# ethernet_jack_cnc_shield.net
KiCad netlist of a schematic drawn in EAGLE
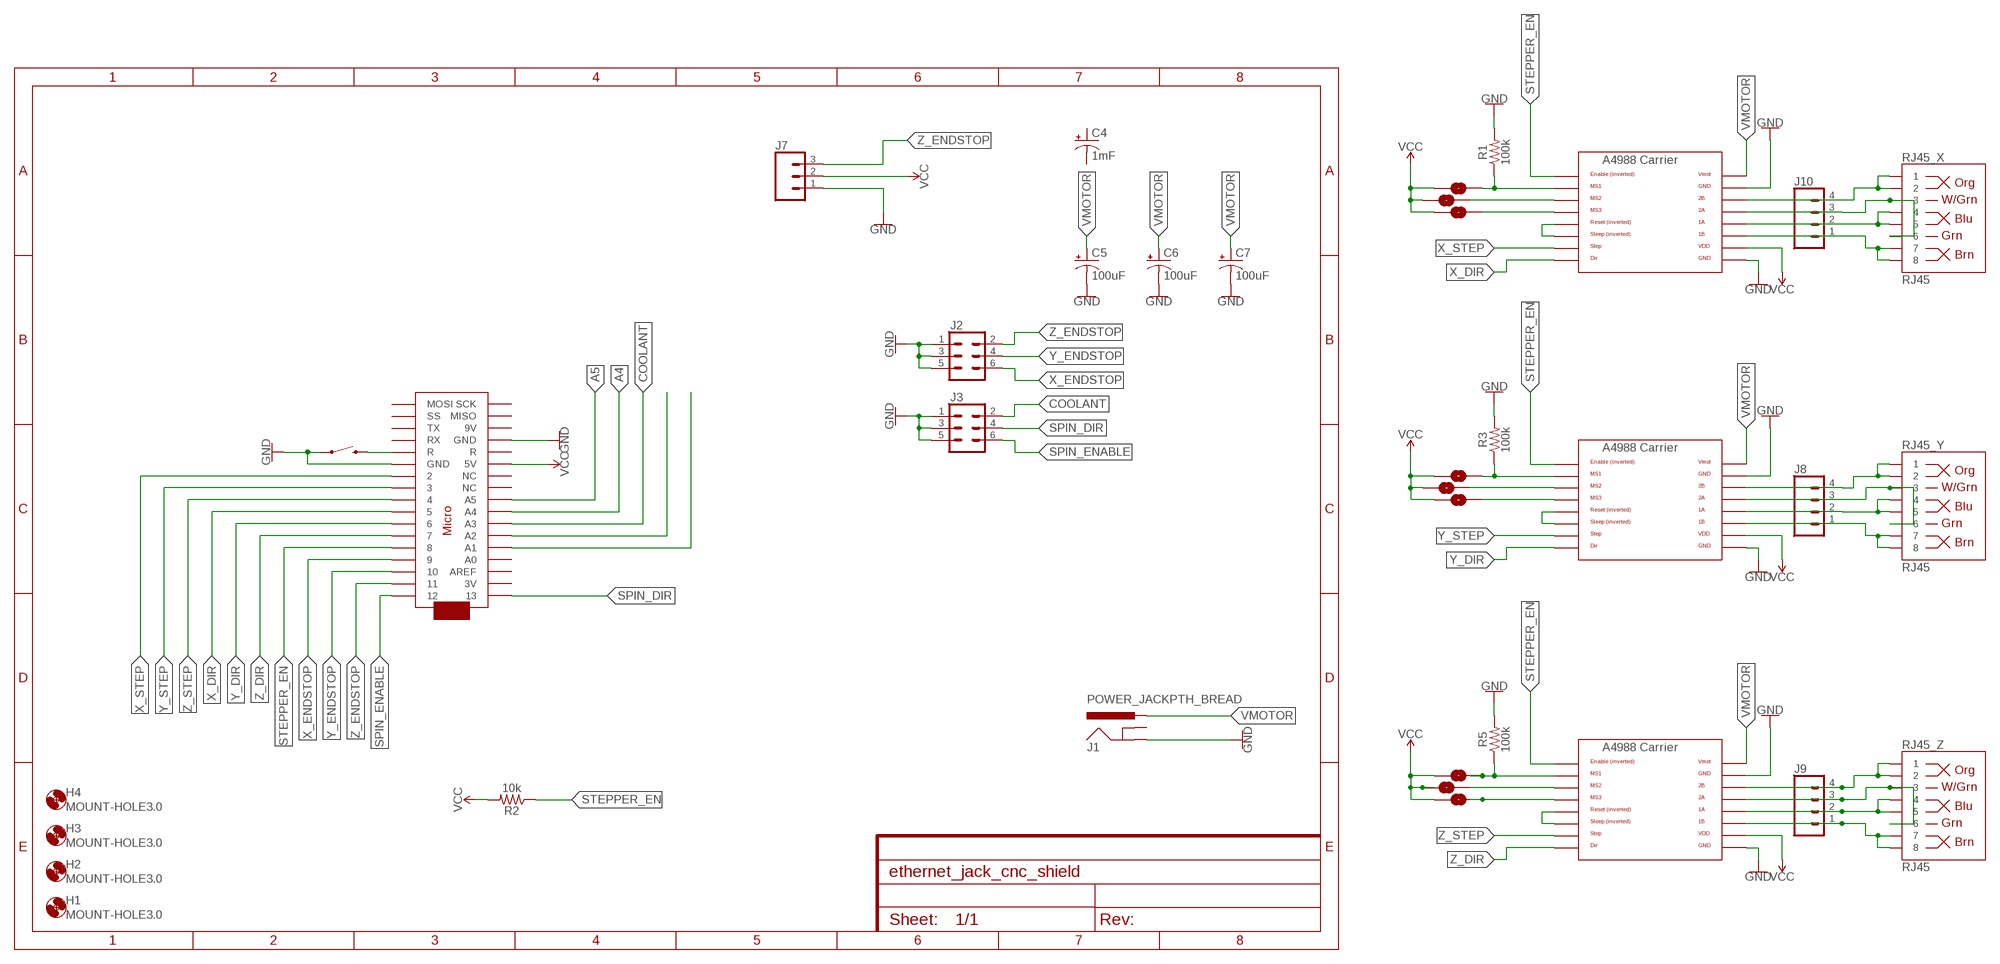
[diagram p0: schematic, sheet 1]

(export (version "E")
  (design (tool "Eeschema 10.0.6"))
  (components
    (comp (ref "C4")
      (value "1mF")
      (footprint "eagle-import:CPOL-RADIAL-5MM-10MM")
      (libsource (lib "eagle-import") (part "1000UF-RADIAL-5MM-25V-20%"))
    )
    (comp (ref "C5")
      (value "100uF")
      (footprint "eagle-import:CPOL-RADIAL-2.5MM-6.5MM")
      (libsource (lib "eagle-import") (part "100UF-POLAR-RADIAL-2.5MM-25V-20%"))
    )
    (comp (ref "C6")
      (value "100uF")
      (footprint "eagle-import:CPOL-RADIAL-2.5MM-6.5MM")
      (libsource (lib "eagle-import") (part "100UF-POLAR-RADIAL-2.5MM-25V-20%"))
    )
    (comp (ref "C7")
      (value "100uF")
      (footprint "eagle-import:CPOL-RADIAL-2.5MM-6.5MM")
      (libsource (lib "eagle-import") (part "100UF-POLAR-RADIAL-2.5MM-25V-20%"))
    )
    (comp (ref "H1")
      (value "MOUNT-HOLE3.0")
      (footprint "eagle-import:3,0")
      (libsource (lib "eagle-import") (part "MOUNT-HOLE3.0"))
    )
    (comp (ref "H2")
      (value "MOUNT-HOLE3.0")
      (footprint "eagle-import:3,0")
      (libsource (lib "eagle-import") (part "MOUNT-HOLE3.0"))
    )
    (comp (ref "H3")
      (value "MOUNT-HOLE3.0")
      (footprint "eagle-import:3,0")
      (libsource (lib "eagle-import") (part "MOUNT-HOLE3.0"))
    )
    (comp (ref "H4")
      (value "MOUNT-HOLE3.0")
      (footprint "eagle-import:3,0")
      (libsource (lib "eagle-import") (part "MOUNT-HOLE3.0"))
    )
    (comp (ref "J1")
      (value "POWER_JACKPTH_BREAD")
      (footprint "eagle-import:POWER_JACK_PTH_BREAD")
      (libsource (lib "eagle-import") (part "POWER_JACKPTH_BREAD"))
    )
    (comp (ref "J2")
      (value "CONN_03X2NO_SILK")
      (footprint "eagle-import:2X3-NS")
      (libsource (lib "eagle-import") (part "CONN_03X2NO_SILK"))
    )
    (comp (ref "J3")
      (value "CONN_03X2NO_SILK")
      (footprint "eagle-import:2X3-NS")
      (libsource (lib "eagle-import") (part "CONN_03X2NO_SILK"))
    )
    (comp (ref "J7")
      (value "CONN_03")
      (footprint "eagle-import:1X03")
      (libsource (lib "eagle-import") (part "CONN_03"))
    )
    (comp (ref "J8")
      (value "CONN_04")
      (footprint "eagle-import:1X04")
      (libsource (lib "eagle-import") (part "CONN_04"))
    )
    (comp (ref "J9")
      (value "CONN_04")
      (footprint "eagle-import:1X04")
      (libsource (lib "eagle-import") (part "CONN_04"))
    )
    (comp (ref "J10")
      (value "CONN_04")
      (footprint "eagle-import:1X04")
      (libsource (lib "eagle-import") (part "CONN_04"))
    )
    (comp (ref "JP1")
      (value "JUMPER-SMT_2_NO_SILK_ROUND")
      (footprint "eagle-import:SMT-JUMPER_2_NO_SILK_ROUND")
      (libsource (lib "eagle-import") (part "JUMPER-SMT_2_NO_SILK_ROUND"))
    )
    (comp (ref "JP2")
      (value "JUMPER-SMT_2_NO_SILK_ROUND")
      (footprint "eagle-import:SMT-JUMPER_2_NO_SILK_ROUND")
      (libsource (lib "eagle-import") (part "JUMPER-SMT_2_NO_SILK_ROUND"))
    )
    (comp (ref "JP3")
      (value "JUMPER-SMT_2_NO_SILK_ROUND")
      (footprint "eagle-import:SMT-JUMPER_2_NO_SILK_ROUND")
      (libsource (lib "eagle-import") (part "JUMPER-SMT_2_NO_SILK_ROUND"))
    )
    (comp (ref "JP4")
      (value "JUMPER-SMT_2_NO_SILK_ROUND")
      (footprint "eagle-import:SMT-JUMPER_2_NO_SILK_ROUND")
      (libsource (lib "eagle-import") (part "JUMPER-SMT_2_NO_SILK_ROUND"))
    )
    (comp (ref "JP5")
      (value "JUMPER-SMT_2_NO_SILK_ROUND")
      (footprint "eagle-import:SMT-JUMPER_2_NO_SILK_ROUND")
      (libsource (lib "eagle-import") (part "JUMPER-SMT_2_NO_SILK_ROUND"))
    )
    (comp (ref "JP6")
      (value "JUMPER-SMT_2_NO_SILK_ROUND")
      (footprint "eagle-import:SMT-JUMPER_2_NO_SILK_ROUND")
      (libsource (lib "eagle-import") (part "JUMPER-SMT_2_NO_SILK_ROUND"))
    )
    (comp (ref "JP7")
      (value "JUMPER-SMT_2_NO_SILK_ROUND")
      (footprint "eagle-import:SMT-JUMPER_2_NO_SILK_ROUND")
      (libsource (lib "eagle-import") (part "JUMPER-SMT_2_NO_SILK_ROUND"))
    )
    (comp (ref "JP8")
      (value "JUMPER-SMT_2_NO_SILK_ROUND")
      (footprint "eagle-import:SMT-JUMPER_2_NO_SILK_ROUND")
      (libsource (lib "eagle-import") (part "JUMPER-SMT_2_NO_SILK_ROUND"))
    )
    (comp (ref "JP9")
      (value "JUMPER-SMT_2_NO_SILK_ROUND")
      (footprint "eagle-import:SMT-JUMPER_2_NO_SILK_ROUND")
      (libsource (lib "eagle-import") (part "JUMPER-SMT_2_NO_SILK_ROUND"))
    )
    (comp (ref "R1")
      (value "100k")
      (footprint "eagle-import:1206")
      (libsource (lib "eagle-import") (part "RESISTOR1206"))
    )
    (comp (ref "R2")
      (value "10k")
      (footprint "eagle-import:1206")
      (libsource (lib "eagle-import") (part "RESISTOR1206"))
    )
    (comp (ref "R3")
      (value "100k")
      (footprint "eagle-import:1206")
      (libsource (lib "eagle-import") (part "RESISTOR1206"))
    )
    (comp (ref "R5")
      (value "100k")
      (footprint "eagle-import:1206")
      (libsource (lib "eagle-import") (part "RESISTOR1206"))
    )
    (comp (ref "RJ45_X")
      (value "RJ45")
      (footprint "eagle-import:RJ45-8")
      (libsource (lib "eagle-import") (part "RJ45-8"))
    )
    (comp (ref "RJ45_Y")
      (value "RJ45")
      (footprint "eagle-import:RJ45-8")
      (libsource (lib "eagle-import") (part "RJ45-8"))
    )
    (comp (ref "RJ45_Z")
      (value "RJ45")
      (footprint "eagle-import:RJ45-8")
      (libsource (lib "eagle-import") (part "RJ45-8"))
    )
    (comp (ref "S1")
      (value "MOMENTARY-SWITCH-SPST-PTH-RIGHT-ANGLE-KIT")
      (footprint "eagle-import:TACTILE_SWITCH_PTH_RIGHT_ANGLE_KIT")
      (libsource (lib "eagle-import") (part "MOMENTARY-SWITCH-SPST-PTH-RIGHT-ANGLE-KIT"))
    )
    (comp (ref "U$1")
      (value "ARDUINOMICRO")
      (footprint "eagle-import:ARDUINOMICRO")
      (libsource (lib "eagle-import") (part "ARDUINOMICRO"))
    )
    (comp (ref "U$2")
      (value "A4988BREAKOUT")
      (footprint "eagle-import:A4988BREAKOUT")
      (libsource (lib "eagle-import") (part "A4988BREAKOUT"))
    )
    (comp (ref "U$3")
      (value "A4988BREAKOUT")
      (footprint "eagle-import:A4988BREAKOUT")
      (libsource (lib "eagle-import") (part "A4988BREAKOUT"))
    )
    (comp (ref "U$4")
      (value "A4988BREAKOUT")
      (footprint "eagle-import:A4988BREAKOUT")
      (libsource (lib "eagle-import") (part "A4988BREAKOUT"))
    )
  )
  (nets
    (net (code "1") (name "A4") (class "Default")
      (node (ref "U$1") (pin "P$27") (pinfunction "A4_P$27") (pintype "bidirectional"))
    )
    (net (code "2") (name "A5") (class "Default")
      (node (ref "U$1") (pin "P$26") (pinfunction "A5_P$26") (pintype "bidirectional"))
    )
    (net (code "3") (name "COOLANT") (class "Default")
      (node (ref "J3") (pin "2") (pinfunction "2_2") (pintype "bidirectional"))
      (node (ref "U$1") (pin "P$28") (pinfunction "A3_P$28") (pintype "bidirectional"))
    )
    (net (code "4") (name "GND") (class "Default")
      (node (ref "C5") (pin "2") (pinfunction "-_2") (pintype "passive"))
      (node (ref "C6") (pin "2") (pinfunction "-_2") (pintype "passive"))
      (node (ref "C7") (pin "2") (pinfunction "-_2") (pintype "passive"))
      (node (ref "J1") (pin "GND") (pinfunction "GND_GND") (pintype "bidirectional"))
      (node (ref "J2") (pin "1") (pinfunction "1_1") (pintype "bidirectional"))
      (node (ref "J2") (pin "3") (pinfunction "3_3") (pintype "bidirectional"))
      (node (ref "J2") (pin "5") (pinfunction "5_5") (pintype "bidirectional"))
      (node (ref "J3") (pin "1") (pinfunction "1_1") (pintype "bidirectional"))
      (node (ref "J3") (pin "3") (pinfunction "3_3") (pintype "bidirectional"))
      (node (ref "J3") (pin "5") (pinfunction "5_5") (pintype "bidirectional"))
      (node (ref "J7") (pin "1") (pinfunction "1_1") (pintype "passive"))
      (node (ref "R1") (pin "2") (pinfunction "2_2") (pintype "passive"))
      (node (ref "R3") (pin "2") (pinfunction "2_2") (pintype "passive"))
      (node (ref "R5") (pin "2") (pinfunction "2_2") (pintype "passive"))
      (node (ref "S1") (pin "1") (pinfunction "1_1") (pintype "passive"))
      (node (ref "U$1") (pin "P$12") (pinfunction "GND_P$12") (pintype "bidirectional"))
      (node (ref "U$1") (pin "P$21") (pinfunction "GND_P$21") (pintype "bidirectional"))
      (node (ref "U$2") (pin "GND") (pinfunction "GND_GND") (pintype "power_in"))
      (node (ref "U$2") (pin "GND@0") (pinfunction "GND_GND@0") (pintype "power_in"))
      (node (ref "U$3") (pin "GND") (pinfunction "GND_GND") (pintype "power_in"))
      (node (ref "U$3") (pin "GND@0") (pinfunction "GND_GND@0") (pintype "power_in"))
      (node (ref "U$4") (pin "GND") (pinfunction "GND_GND") (pintype "power_in"))
      (node (ref "U$4") (pin "GND@0") (pinfunction "GND_GND@0") (pintype "power_in"))
    )
    (net (code "5") (name "Net-(J8-Pad1)") (class "Default")
      (node (ref "J8") (pin "1") (pinfunction "1_1") (pintype "passive"))
      (node (ref "RJ45_Y") (pin "7") (pinfunction "7_7") (pintype "bidirectional"))
      (node (ref "RJ45_Y") (pin "8") (pinfunction "8_8") (pintype "bidirectional"))
      (node (ref "U$2") (pin "1B") (pinfunction "1B_1B") (pintype "output"))
    )
    (net (code "6") (name "Net-(J8-Pad2)") (class "Default")
      (node (ref "J8") (pin "2") (pinfunction "2_2") (pintype "passive"))
      (node (ref "RJ45_Y") (pin "4") (pinfunction "4_4") (pintype "bidirectional"))
      (node (ref "RJ45_Y") (pin "5") (pinfunction "5_5") (pintype "bidirectional"))
      (node (ref "U$2") (pin "1A") (pinfunction "1A_1A") (pintype "output"))
    )
    (net (code "7") (name "Net-(J8-Pad3)") (class "Default")
      (node (ref "J8") (pin "3") (pinfunction "3_3") (pintype "passive"))
      (node (ref "RJ45_Y") (pin "3") (pinfunction "3_3") (pintype "bidirectional"))
      (node (ref "RJ45_Y") (pin "6") (pinfunction "6_6") (pintype "bidirectional"))
      (node (ref "U$2") (pin "2A") (pinfunction "2A_2A") (pintype "output"))
    )
    (net (code "8") (name "Net-(J8-Pad4)") (class "Default")
      (node (ref "J8") (pin "4") (pinfunction "4_4") (pintype "passive"))
      (node (ref "RJ45_Y") (pin "1") (pinfunction "1_1") (pintype "bidirectional"))
      (node (ref "RJ45_Y") (pin "2") (pinfunction "2_2") (pintype "bidirectional"))
      (node (ref "U$2") (pin "2B") (pinfunction "2B_2B") (pintype "output"))
    )
    (net (code "9") (name "Net-(J9-Pad1)") (class "Default")
      (node (ref "J9") (pin "1") (pinfunction "1_1") (pintype "passive"))
      (node (ref "RJ45_Z") (pin "7") (pinfunction "7_7") (pintype "bidirectional"))
      (node (ref "RJ45_Z") (pin "8") (pinfunction "8_8") (pintype "bidirectional"))
      (node (ref "U$3") (pin "1B") (pinfunction "1B_1B") (pintype "output"))
    )
    (net (code "10") (name "Net-(J9-Pad2)") (class "Default")
      (node (ref "J9") (pin "2") (pinfunction "2_2") (pintype "passive"))
      (node (ref "RJ45_Z") (pin "4") (pinfunction "4_4") (pintype "bidirectional"))
      (node (ref "RJ45_Z") (pin "5") (pinfunction "5_5") (pintype "bidirectional"))
      (node (ref "U$3") (pin "1A") (pinfunction "1A_1A") (pintype "output"))
    )
    (net (code "11") (name "Net-(J9-Pad3)") (class "Default")
      (node (ref "J9") (pin "3") (pinfunction "3_3") (pintype "passive"))
      (node (ref "RJ45_Z") (pin "3") (pinfunction "3_3") (pintype "bidirectional"))
      (node (ref "RJ45_Z") (pin "6") (pinfunction "6_6") (pintype "bidirectional"))
      (node (ref "U$3") (pin "2A") (pinfunction "2A_2A") (pintype "output"))
    )
    (net (code "12") (name "Net-(J9-Pad4)") (class "Default")
      (node (ref "J9") (pin "4") (pinfunction "4_4") (pintype "passive"))
      (node (ref "RJ45_Z") (pin "1") (pinfunction "1_1") (pintype "bidirectional"))
      (node (ref "RJ45_Z") (pin "2") (pinfunction "2_2") (pintype "bidirectional"))
      (node (ref "U$3") (pin "2B") (pinfunction "2B_2B") (pintype "output"))
    )
    (net (code "13") (name "Net-(J10-Pad1)") (class "Default")
      (node (ref "J10") (pin "1") (pinfunction "1_1") (pintype "passive"))
      (node (ref "RJ45_X") (pin "7") (pinfunction "7_7") (pintype "bidirectional"))
      (node (ref "RJ45_X") (pin "8") (pinfunction "8_8") (pintype "bidirectional"))
      (node (ref "U$4") (pin "1B") (pinfunction "1B_1B") (pintype "output"))
    )
    (net (code "14") (name "Net-(J10-Pad2)") (class "Default")
      (node (ref "J10") (pin "2") (pinfunction "2_2") (pintype "passive"))
      (node (ref "RJ45_X") (pin "4") (pinfunction "4_4") (pintype "bidirectional"))
      (node (ref "RJ45_X") (pin "5") (pinfunction "5_5") (pintype "bidirectional"))
      (node (ref "U$4") (pin "1A") (pinfunction "1A_1A") (pintype "output"))
    )
    (net (code "15") (name "Net-(J10-Pad3)") (class "Default")
      (node (ref "J10") (pin "3") (pinfunction "3_3") (pintype "passive"))
      (node (ref "RJ45_X") (pin "3") (pinfunction "3_3") (pintype "bidirectional"))
      (node (ref "RJ45_X") (pin "6") (pinfunction "6_6") (pintype "bidirectional"))
      (node (ref "U$4") (pin "2A") (pinfunction "2A_2A") (pintype "output"))
    )
    (net (code "16") (name "Net-(J10-Pad4)") (class "Default")
      (node (ref "J10") (pin "4") (pinfunction "4_4") (pintype "passive"))
      (node (ref "RJ45_X") (pin "1") (pinfunction "1_1") (pintype "bidirectional"))
      (node (ref "RJ45_X") (pin "2") (pinfunction "2_2") (pintype "bidirectional"))
      (node (ref "U$4") (pin "2B") (pinfunction "2B_2B") (pintype "output"))
    )
    (net (code "17") (name "Net-(JP1-Pad2)") (class "Default")
      (node (ref "JP1") (pin "2") (pinfunction "2_2") (pintype "passive"))
      (node (ref "R3") (pin "1") (pinfunction "1_1") (pintype "passive"))
      (node (ref "U$2") (pin "MS1") (pinfunction "MS1_MS1") (pintype "input"))
    )
    (net (code "18") (name "Net-(JP2-Pad2)") (class "Default")
      (node (ref "JP2") (pin "2") (pinfunction "2_2") (pintype "passive"))
      (node (ref "U$2") (pin "MS2") (pinfunction "MS2_MS2") (pintype "input"))
    )
    (net (code "19") (name "Net-(JP3-Pad2)") (class "Default")
      (node (ref "JP3") (pin "2") (pinfunction "2_2") (pintype "passive"))
      (node (ref "R5") (pin "1") (pinfunction "1_1") (pintype "passive"))
      (node (ref "U$3") (pin "MS1") (pinfunction "MS1_MS1") (pintype "input"))
    )
    (net (code "20") (name "Net-(JP4-Pad2)") (class "Default")
      (node (ref "JP4") (pin "2") (pinfunction "2_2") (pintype "passive"))
      (node (ref "R1") (pin "1") (pinfunction "1_1") (pintype "passive"))
      (node (ref "U$4") (pin "MS1") (pinfunction "MS1_MS1") (pintype "input"))
    )
    (net (code "21") (name "Net-(JP5-Pad2)") (class "Default")
      (node (ref "JP5") (pin "2") (pinfunction "2_2") (pintype "passive"))
      (node (ref "U$4") (pin "MS2") (pinfunction "MS2_MS2") (pintype "input"))
    )
    (net (code "22") (name "Net-(JP6-Pad2)") (class "Default")
      (node (ref "JP6") (pin "2") (pinfunction "2_2") (pintype "passive"))
      (node (ref "U$4") (pin "MS3") (pinfunction "MS3_MS3") (pintype "input"))
    )
    (net (code "23") (name "Net-(JP7-Pad2)") (class "Default")
      (node (ref "JP7") (pin "2") (pinfunction "2_2") (pintype "passive"))
      (node (ref "U$2") (pin "MS3") (pinfunction "MS3_MS3") (pintype "input"))
    )
    (net (code "24") (name "Net-(JP8-Pad2)") (class "Default")
      (node (ref "JP8") (pin "2") (pinfunction "2_2") (pintype "passive"))
      (node (ref "U$3") (pin "MS2") (pinfunction "MS2_MS2") (pintype "input"))
    )
    (net (code "25") (name "Net-(JP9-Pad2)") (class "Default")
      (node (ref "JP9") (pin "2") (pinfunction "2_2") (pintype "passive"))
      (node (ref "U$3") (pin "MS3") (pinfunction "MS3_MS3") (pintype "input"))
    )
    (net (code "26") (name "Net-(S1-Pad2)") (class "Default")
      (node (ref "S1") (pin "2") (pinfunction "2_2") (pintype "passive"))
      (node (ref "U$1") (pin "P$22") (pinfunction "R_P$22") (pintype "bidirectional"))
    )
    (net (code "27") (name "Net-(U$2-SLEEP)") (class "Default")
      (node (ref "U$2") (pin "RST") (pinfunction "RST_RST") (pintype "input"))
      (node (ref "U$2") (pin "SLP") (pinfunction "SLEEP_SLP") (pintype "input"))
    )
    (net (code "28") (name "Net-(U$3-SLEEP)") (class "Default")
      (node (ref "U$3") (pin "RST") (pinfunction "RST_RST") (pintype "input"))
      (node (ref "U$3") (pin "SLP") (pinfunction "SLEEP_SLP") (pintype "input"))
    )
    (net (code "29") (name "Net-(U$4-SLEEP)") (class "Default")
      (node (ref "U$4") (pin "RST") (pinfunction "RST_RST") (pintype "input"))
      (node (ref "U$4") (pin "SLP") (pinfunction "SLEEP_SLP") (pintype "input"))
    )
    (net (code "30") (name "SPIN_DIR") (class "Default")
      (node (ref "J3") (pin "4") (pinfunction "4_4") (pintype "bidirectional"))
      (node (ref "U$1") (pin "P$34") (pinfunction "13_P$34") (pintype "bidirectional"))
    )
    (net (code "31") (name "SPIN_ENABLE") (class "Default")
      (node (ref "J3") (pin "6") (pinfunction "6_6") (pintype "bidirectional"))
      (node (ref "U$1") (pin "P$1") (pinfunction "12_P$1") (pintype "bidirectional"))
    )
    (net (code "32") (name "STEPPER_EN") (class "Default")
      (node (ref "R2") (pin "1") (pinfunction "1_1") (pintype "passive"))
      (node (ref "U$1") (pin "P$5") (pinfunction "8_P$5") (pintype "bidirectional"))
      (node (ref "U$2") (pin "EN") (pinfunction "EN_EN") (pintype "input"))
      (node (ref "U$3") (pin "EN") (pinfunction "EN_EN") (pintype "input"))
      (node (ref "U$4") (pin "EN") (pinfunction "EN_EN") (pintype "input"))
    )
    (net (code "33") (name "VCC") (class "Default")
      (node (ref "J7") (pin "2") (pinfunction "2_2") (pintype "passive"))
      (node (ref "JP1") (pin "1") (pinfunction "1_1") (pintype "passive"))
      (node (ref "JP2") (pin "1") (pinfunction "1_1") (pintype "passive"))
      (node (ref "JP3") (pin "1") (pinfunction "1_1") (pintype "passive"))
      (node (ref "JP4") (pin "1") (pinfunction "1_1") (pintype "passive"))
      (node (ref "JP5") (pin "1") (pinfunction "1_1") (pintype "passive"))
      (node (ref "JP6") (pin "1") (pinfunction "1_1") (pintype "passive"))
      (node (ref "JP7") (pin "1") (pinfunction "1_1") (pintype "passive"))
      (node (ref "JP8") (pin "1") (pinfunction "1_1") (pintype "passive"))
      (node (ref "JP9") (pin "1") (pinfunction "1_1") (pintype "passive"))
      (node (ref "R2") (pin "2") (pinfunction "2_2") (pintype "passive"))
      (node (ref "U$1") (pin "P$23") (pinfunction "5V_P$23") (pintype "bidirectional"))
      (node (ref "U$2") (pin "VDD") (pinfunction "VDD_VDD") (pintype "power_in"))
      (node (ref "U$3") (pin "VDD") (pinfunction "VDD_VDD") (pintype "power_in"))
      (node (ref "U$4") (pin "VDD") (pinfunction "VDD_VDD") (pintype "power_in"))
    )
    (net (code "34") (name "VMOTOR") (class "Default")
      (node (ref "C5") (pin "1") (pinfunction "+_1") (pintype "passive"))
      (node (ref "C6") (pin "1") (pinfunction "+_1") (pintype "passive"))
      (node (ref "C7") (pin "1") (pinfunction "+_1") (pintype "passive"))
      (node (ref "J1") (pin "PWR") (pinfunction "PWR_PWR") (pintype "bidirectional"))
      (node (ref "U$2") (pin "VMOT") (pinfunction "VMOT_VMOT") (pintype "power_in"))
      (node (ref "U$3") (pin "VMOT") (pinfunction "VMOT_VMOT") (pintype "power_in"))
      (node (ref "U$4") (pin "VMOT") (pinfunction "VMOT_VMOT") (pintype "power_in"))
    )
    (net (code "35") (name "X_DIR") (class "Default")
      (node (ref "U$1") (pin "P$8") (pinfunction "5_P$8") (pintype "bidirectional"))
      (node (ref "U$4") (pin "DIR") (pinfunction "DIR_DIR") (pintype "input"))
    )
    (net (code "36") (name "X_ENDSTOP") (class "Default")
      (node (ref "J2") (pin "6") (pinfunction "6_6") (pintype "bidirectional"))
      (node (ref "U$1") (pin "P$4") (pinfunction "9_P$4") (pintype "bidirectional"))
    )
    (net (code "37") (name "X_STEP") (class "Default")
      (node (ref "U$1") (pin "P$11") (pinfunction "2_P$11") (pintype "bidirectional"))
      (node (ref "U$4") (pin "STEP") (pinfunction "STEP_STEP") (pintype "input"))
    )
    (net (code "38") (name "Y_DIR") (class "Default")
      (node (ref "U$1") (pin "P$7") (pinfunction "6_P$7") (pintype "bidirectional"))
      (node (ref "U$2") (pin "DIR") (pinfunction "DIR_DIR") (pintype "input"))
    )
    (net (code "39") (name "Y_ENDSTOP") (class "Default")
      (node (ref "J2") (pin "4") (pinfunction "4_4") (pintype "bidirectional"))
      (node (ref "U$1") (pin "P$3") (pinfunction "10_P$3") (pintype "bidirectional"))
    )
    (net (code "40") (name "Y_STEP") (class "Default")
      (node (ref "U$1") (pin "P$10") (pinfunction "3_P$10") (pintype "bidirectional"))
      (node (ref "U$2") (pin "STEP") (pinfunction "STEP_STEP") (pintype "input"))
    )
    (net (code "41") (name "Z_DIR") (class "Default")
      (node (ref "U$1") (pin "P$6") (pinfunction "7_P$6") (pintype "bidirectional"))
      (node (ref "U$3") (pin "DIR") (pinfunction "DIR_DIR") (pintype "input"))
    )
    (net (code "42") (name "Z_ENDSTOP") (class "Default")
      (node (ref "J2") (pin "2") (pinfunction "2_2") (pintype "bidirectional"))
      (node (ref "J7") (pin "3") (pinfunction "3_3") (pintype "passive"))
      (node (ref "U$1") (pin "P$2") (pinfunction "11_P$2") (pintype "bidirectional"))
    )
    (net (code "43") (name "Z_STEP") (class "Default")
      (node (ref "U$1") (pin "P$9") (pinfunction "4_P$9") (pintype "bidirectional"))
      (node (ref "U$3") (pin "STEP") (pinfunction "STEP_STEP") (pintype "input"))
    )
    (net (code "44") (name "unconnected-(C4-Pad+)") (class "Default")
      (node (ref "C4") (pin "+") (pinfunction "+_+") (pintype "passive"))
    )
    (net (code "45") (name "unconnected-(C4-Pad-)") (class "Default")
      (node (ref "C4") (pin "-") (pinfunction "-_-") (pintype "passive"))
    )
    (net (code "46") (name "unconnected-(J1-PadGNDBREAK)") (class "Default")
      (node (ref "J1") (pin "GNDBREAK") (pinfunction "GNDBREAK_GNDBREAK") (pintype "bidirectional"))
    )
    (net (code "47") (name "unconnected-(U$1-3V-PadP$33)") (class "Default")
      (node (ref "U$1") (pin "P$33") (pinfunction "3V_P$33") (pintype "bidirectional"))
    )
    (net (code "48") (name "unconnected-(U$1-9V-PadP$20)") (class "Default")
      (node (ref "U$1") (pin "P$20") (pinfunction "9V_P$20") (pintype "bidirectional"))
    )
    (net (code "49") (name "unconnected-(U$1-A0-PadP$31)") (class "Default")
      (node (ref "U$1") (pin "P$31") (pinfunction "A0_P$31") (pintype "bidirectional"))
    )
    (net (code "50") (name "unconnected-(U$1-A1-PadP$30)") (class "Default")
      (node (ref "U$1") (pin "P$30") (pinfunction "A1_P$30") (pintype "bidirectional"))
    )
    (net (code "51") (name "unconnected-(U$1-A2-PadP$29)") (class "Default")
      (node (ref "U$1") (pin "P$29") (pinfunction "A2_P$29") (pintype "bidirectional"))
    )
    (net (code "52") (name "unconnected-(U$1-AREF-PadP$32)") (class "Default")
      (node (ref "U$1") (pin "P$32") (pinfunction "AREF_P$32") (pintype "bidirectional"))
    )
    (net (code "53") (name "unconnected-(U$1-MISO-PadP$19)") (class "Default")
      (node (ref "U$1") (pin "P$19") (pinfunction "MISO_P$19") (pintype "bidirectional"))
    )
    (net (code "54") (name "unconnected-(U$1-MOSI-PadP$17)") (class "Default")
      (node (ref "U$1") (pin "P$17") (pinfunction "MOSI_P$17") (pintype "bidirectional"))
    )
    (net (code "55") (name "unconnected-(U$1-NC-PadP$24)") (class "Default")
      (node (ref "U$1") (pin "P$24") (pinfunction "NC_P$24") (pintype "bidirectional"))
    )
    (net (code "56") (name "unconnected-(U$1-NC-PadP$25)") (class "Default")
      (node (ref "U$1") (pin "P$25") (pinfunction "NC_P$25") (pintype "bidirectional"))
    )
    (net (code "57") (name "unconnected-(U$1-R-PadP$13)") (class "Default")
      (node (ref "U$1") (pin "P$13") (pinfunction "R_P$13") (pintype "bidirectional"))
    )
    (net (code "58") (name "unconnected-(U$1-RX-PadP$14)") (class "Default")
      (node (ref "U$1") (pin "P$14") (pinfunction "RX_P$14") (pintype "bidirectional"))
    )
    (net (code "59") (name "unconnected-(U$1-SCK-PadP$18)") (class "Default")
      (node (ref "U$1") (pin "P$18") (pinfunction "SCK_P$18") (pintype "bidirectional"))
    )
    (net (code "60") (name "unconnected-(U$1-SS-PadP$16)") (class "Default")
      (node (ref "U$1") (pin "P$16") (pinfunction "SS_P$16") (pintype "bidirectional"))
    )
    (net (code "61") (name "unconnected-(U$1-TX-PadP$15)") (class "Default")
      (node (ref "U$1") (pin "P$15") (pinfunction "TX_P$15") (pintype "bidirectional"))
    )
  )
)
